# MDL_RECEPTOR_IRF_2.net
KiCad netlist of a schematic drawn in Altium Designer
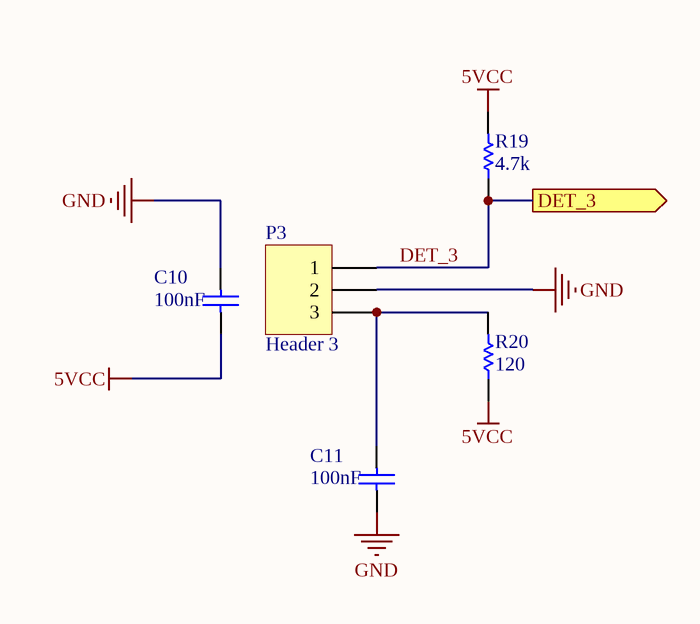
[diagram p0: MDL_RECEPTOR_IRF_2.SchDoc]

(export (version "E")
  (design (tool "Eeschema 10.0.6"))
  (components
    (comp (ref "C10")
      (value "100nF")
      (footprint "VP44-2.5")
      (description "Dipped Radial Multilayer Ceramic Capacitor X7R: 220nF, 100V")
      (fields (field (name "Comment") "VP44BY224JB") (field (name "PUBLISHER") "Altium Limited"))
      (libsource (lib "Vishay Vitramon Ceramic Dipped Capacitor") (part "VP44BY224JB"))
    )
    (comp (ref "C11")
      (value "100nF")
      (footprint "VP44-2.5")
      (description "Dipped Radial Multilayer Ceramic Capacitor X7R: 220nF, 100V")
      (fields (field (name "Comment") "VP44BY224JB") (field (name "PUBLISHER") "Altium Limited"))
      (libsource (lib "Vishay Vitramon Ceramic Dipped Capacitor") (part "VP44BY224JB"))
    )
    (comp (ref "P3")
      (value "Header 3")
      (footprint "HDR1X3")
      (description "Header, 3-Pin")
      (fields (field (name "PUBLISHER") "Altium Limited"))
      (libsource (lib "Miscellaneous Connectors") (part "Header 3"))
    )
    (comp (ref "R19")
      (value "4.7k")
      (footprint "AXIAL-0.3")
      (description "Resistor")
      (fields (field (name "Comment") "Res") (field (name "PUBLISHER") "Altium Limited"))
      (libsource (lib "Miscellaneous Devices") (part "Res1"))
    )
    (comp (ref "R20")
      (value "120")
      (footprint "AXIAL-0.3")
      (description "Resistor")
      (fields (field (name "Comment") "Res") (field (name "PUBLISHER") "Altium Limited"))
      (libsource (lib "Miscellaneous Devices") (part "Res1"))
    )
  )
  (nets
    (net (code "1") (name "/DET_3") (class "Default")
      (node (ref "P3") (pin "1") (pinfunction "1_1") (pintype "passive"))
      (node (ref "R19") (pin "1") (pinfunction "1_1") (pintype "passive"))
    )
    (net (code "2") (name "5VCC") (class "Default")
      (node (ref "C10") (pin "2") (pinfunction "2_2") (pintype "passive"))
      (node (ref "R19") (pin "2") (pinfunction "2_2") (pintype "passive"))
      (node (ref "R20") (pin "1") (pinfunction "1_1") (pintype "passive"))
    )
    (net (code "3") (name "GND") (class "Default")
      (node (ref "C10") (pin "1") (pinfunction "1_1") (pintype "passive"))
      (node (ref "C11") (pin "2") (pinfunction "2_2") (pintype "passive"))
      (node (ref "P3") (pin "2") (pinfunction "2_2") (pintype "passive"))
    )
    (net (code "4") (name "Net-(C11-Pad1)") (class "Default")
      (node (ref "C11") (pin "1") (pinfunction "1_1") (pintype "passive"))
      (node (ref "P3") (pin "3") (pinfunction "3_3") (pintype "passive"))
      (node (ref "R20") (pin "2") (pinfunction "2_2") (pintype "passive"))
    )
  )
)
